# Sheet1.net
KiCad netlist of a schematic drawn in Altium Designer
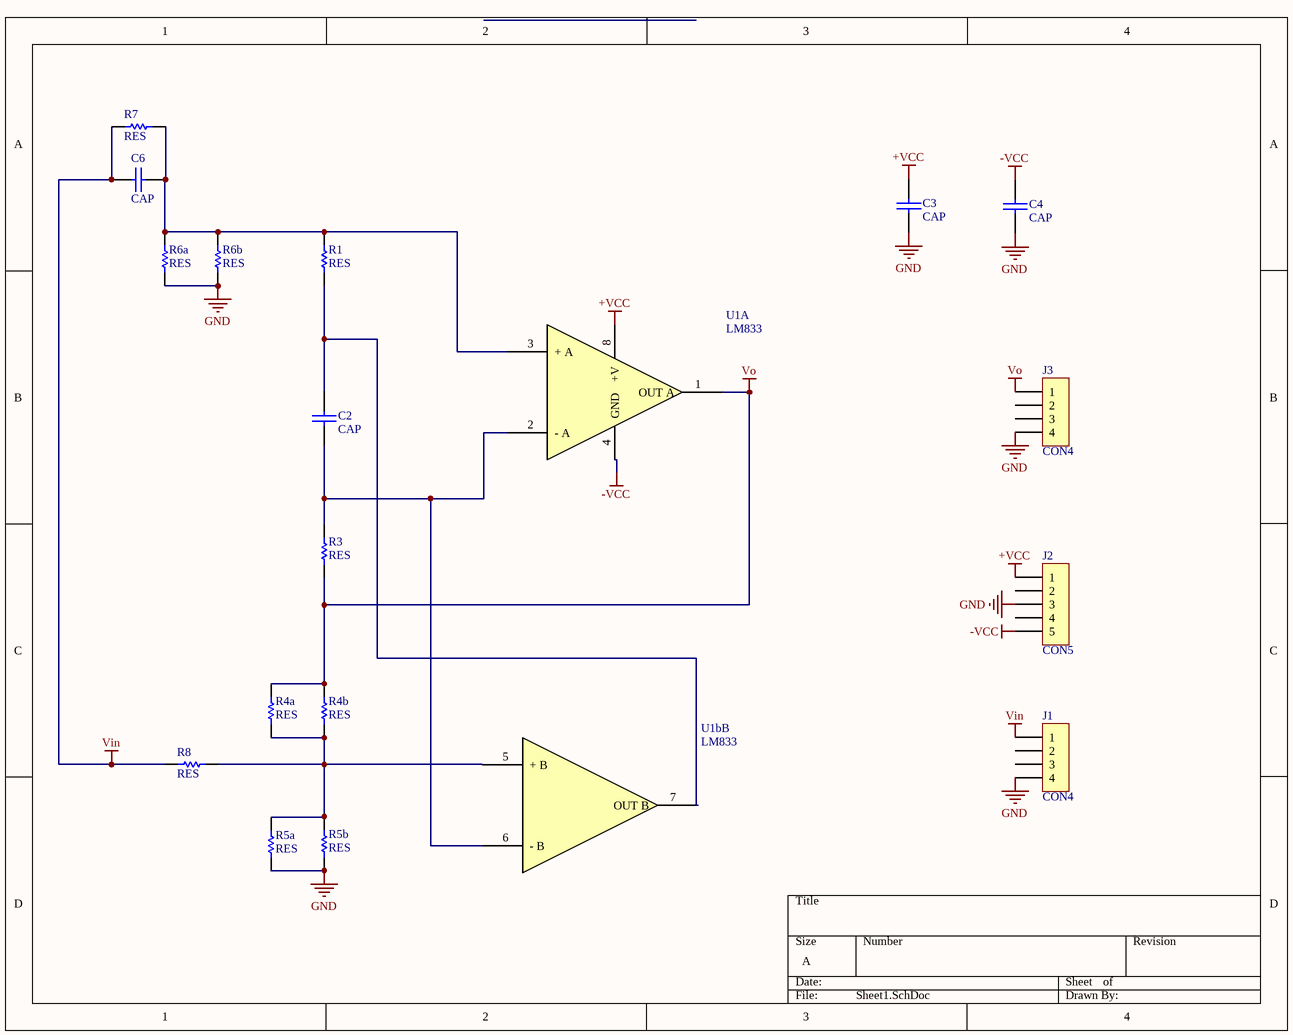
[diagram p0: Sheet1.SchDoc]

(export (version "E")
  (design (tool "Eeschema 10.0.6"))
  (components
    (comp (ref "C2") (value "CAP") (footprint "CAP200") (libsource (lib "LIBEBAL") (part "CAP")))
    (comp (ref "C3") (value "CAP") (footprint "CAP200") (libsource (lib "LIBEBAL") (part "CAP")))
    (comp (ref "C4") (value "CAP") (footprint "CAP200") (libsource (lib "LIBEBAL") (part "CAP")))
    (comp (ref "C6") (value "CAP") (footprint "CAP200") (libsource (lib "LIBEBAL") (part "CAP")))
    (comp (ref "J1") (value "CON4") (footprint "SIP4") (libsource (lib "LIBEBAL") (part "CON4")))
    (comp (ref "J2") (value "CON5") (footprint "SIP5") (libsource (lib "LIBEBAL") (part "CON5")))
    (comp (ref "J3") (value "CON4") (footprint "SIP4") (libsource (lib "LIBEBAL") (part "CON4")))
    (comp (ref "R1") (value "RES") (footprint "0805") (libsource (lib "LIBEBAL") (part "RES")))
    (comp (ref "R3") (value "RES") (footprint "0805") (libsource (lib "LIBEBAL") (part "RES")))
    (comp (ref "R4a") (value "RES") (footprint "0805") (libsource (lib "LIBEBAL") (part "RES")))
    (comp (ref "R4b") (value "RES") (footprint "0805") (libsource (lib "LIBEBAL") (part "RES")))
    (comp (ref "R5a") (value "RES") (footprint "0805") (libsource (lib "LIBEBAL") (part "RES")))
    (comp (ref "R5b") (value "RES") (footprint "0805") (libsource (lib "LIBEBAL") (part "RES")))
    (comp (ref "R6a") (value "RES") (footprint "0805") (libsource (lib "LIBEBAL") (part "RES")))
    (comp (ref "R6b") (value "RES") (footprint "0805") (libsource (lib "LIBEBAL") (part "RES")))
    (comp (ref "R7") (value "RES") (footprint "0805") (libsource (lib "LIBEBAL") (part "RES")))
    (comp (ref "R8") (value "RES") (footprint "0805") (libsource (lib "LIBEBAL") (part "RES")))
    (comp (ref "U1")
      (value "LM833")
      (footprint "DIP8")
      (description "Dual Audio Operational Amplifier")
      (libsource (lib "LIBEBAL") (part "LM833"))
    )
    (comp (ref "U1b")
      (value "LM833")
      (footprint "DIP8")
      (description "Dual Audio Operational Amplifier")
      (libsource (lib "LIBEBAL") (part "LM833"))
    )
  )
  (nets
    (net (code "1") (name "+VCC") (class "Default")
      (node (ref "C3") (pin "1") (pinfunction "1_1") (pintype "passive"))
      (node (ref "J2") (pin "1") (pinfunction "1_1") (pintype "passive"))
      (node (ref "U1") (pin "8") (pinfunction "+V_8") (pintype "passive"))
    )
    (net (code "2") (name "-VCC") (class "Default")
      (node (ref "C4") (pin "1") (pinfunction "1_1") (pintype "passive"))
      (node (ref "J2") (pin "5") (pinfunction "5_5") (pintype "passive"))
      (node (ref "U1") (pin "4") (pinfunction "GND_4") (pintype "passive"))
    )
    (net (code "3") (name "GND") (class "Default")
      (node (ref "C3") (pin "2") (pinfunction "2_2") (pintype "passive"))
      (node (ref "C4") (pin "2") (pinfunction "2_2") (pintype "passive"))
      (node (ref "J1") (pin "4") (pinfunction "4_4") (pintype "passive"))
      (node (ref "J2") (pin "3") (pinfunction "3_3") (pintype "passive"))
      (node (ref "J3") (pin "4") (pinfunction "4_4") (pintype "passive"))
      (node (ref "R5a") (pin "1") (pinfunction "1_1") (pintype "passive"))
      (node (ref "R5b") (pin "1") (pinfunction "1_1") (pintype "passive"))
      (node (ref "R6a") (pin "1") (pinfunction "1_1") (pintype "passive"))
      (node (ref "R6b") (pin "1") (pinfunction "1_1") (pintype "passive"))
    )
    (net (code "4") (name "Net-(U1A-+_A)") (class "Default")
      (node (ref "C6") (pin "2") (pinfunction "2_2") (pintype "passive"))
      (node (ref "R1") (pin "2") (pinfunction "2_2") (pintype "passive"))
      (node (ref "R6a") (pin "2") (pinfunction "2_2") (pintype "passive"))
      (node (ref "R6b") (pin "2") (pinfunction "2_2") (pintype "passive"))
      (node (ref "R7") (pin "2") (pinfunction "2_2") (pintype "passive"))
      (node (ref "U1") (pin "3") (pinfunction "+_A_3") (pintype "passive"))
    )
    (net (code "5") (name "Net-(U1A--_A)") (class "Default")
      (node (ref "C2") (pin "2") (pinfunction "2_2") (pintype "passive"))
      (node (ref "R3") (pin "2") (pinfunction "2_2") (pintype "passive"))
      (node (ref "U1") (pin "2") (pinfunction "-_A_2") (pintype "passive"))
      (node (ref "U1b") (pin "6") (pinfunction "-_B_6") (pintype "passive"))
    )
    (net (code "6") (name "Net-(U1bB-+_B)") (class "Default")
      (node (ref "R4a") (pin "1") (pinfunction "1_1") (pintype "passive"))
      (node (ref "R4b") (pin "1") (pinfunction "1_1") (pintype "passive"))
      (node (ref "R5a") (pin "2") (pinfunction "2_2") (pintype "passive"))
      (node (ref "R5b") (pin "2") (pinfunction "2_2") (pintype "passive"))
      (node (ref "R8") (pin "2") (pinfunction "2_2") (pintype "passive"))
      (node (ref "U1b") (pin "5") (pinfunction "+_B_5") (pintype "passive"))
    )
    (net (code "7") (name "Net-(U1bB-OUT_B)") (class "Default")
      (node (ref "C2") (pin "1") (pinfunction "1_1") (pintype "passive"))
      (node (ref "R1") (pin "1") (pinfunction "1_1") (pintype "passive"))
      (node (ref "U1b") (pin "7") (pinfunction "OUT_B_7") (pintype "passive"))
    )
    (net (code "8") (name "Vin") (class "Default")
      (node (ref "C6") (pin "1") (pinfunction "1_1") (pintype "passive"))
      (node (ref "J1") (pin "1") (pinfunction "1_1") (pintype "passive"))
      (node (ref "R7") (pin "1") (pinfunction "1_1") (pintype "passive"))
      (node (ref "R8") (pin "1") (pinfunction "1_1") (pintype "passive"))
    )
    (net (code "9") (name "Vo") (class "Default")
      (node (ref "J3") (pin "1") (pinfunction "1_1") (pintype "passive"))
      (node (ref "R3") (pin "1") (pinfunction "1_1") (pintype "passive"))
      (node (ref "R4a") (pin "2") (pinfunction "2_2") (pintype "passive"))
      (node (ref "R4b") (pin "2") (pinfunction "2_2") (pintype "passive"))
      (node (ref "U1") (pin "1") (pinfunction "OUT_A_1") (pintype "passive"))
    )
    (net (code "10") (name "unconnected-(J1-Pad2)") (class "Default")
      (node (ref "J1") (pin "2") (pinfunction "2_2") (pintype "passive"))
    )
    (net (code "11") (name "unconnected-(J1-Pad3)") (class "Default")
      (node (ref "J1") (pin "3") (pinfunction "3_3") (pintype "passive"))
    )
    (net (code "12") (name "unconnected-(J2-Pad2)") (class "Default")
      (node (ref "J2") (pin "2") (pinfunction "2_2") (pintype "passive"))
    )
    (net (code "13") (name "unconnected-(J2-Pad4)") (class "Default")
      (node (ref "J2") (pin "4") (pinfunction "4_4") (pintype "passive"))
    )
    (net (code "14") (name "unconnected-(J3-Pad2)") (class "Default")
      (node (ref "J3") (pin "2") (pinfunction "2_2") (pintype "passive"))
    )
    (net (code "15") (name "unconnected-(J3-Pad3)") (class "Default")
      (node (ref "J3") (pin "3") (pinfunction "3_3") (pintype "passive"))
    )
  )
)
